# MCH_FPGA_Banks_224_225_226_227_228.net
KiCad netlist of a schematic drawn in Altium Designer
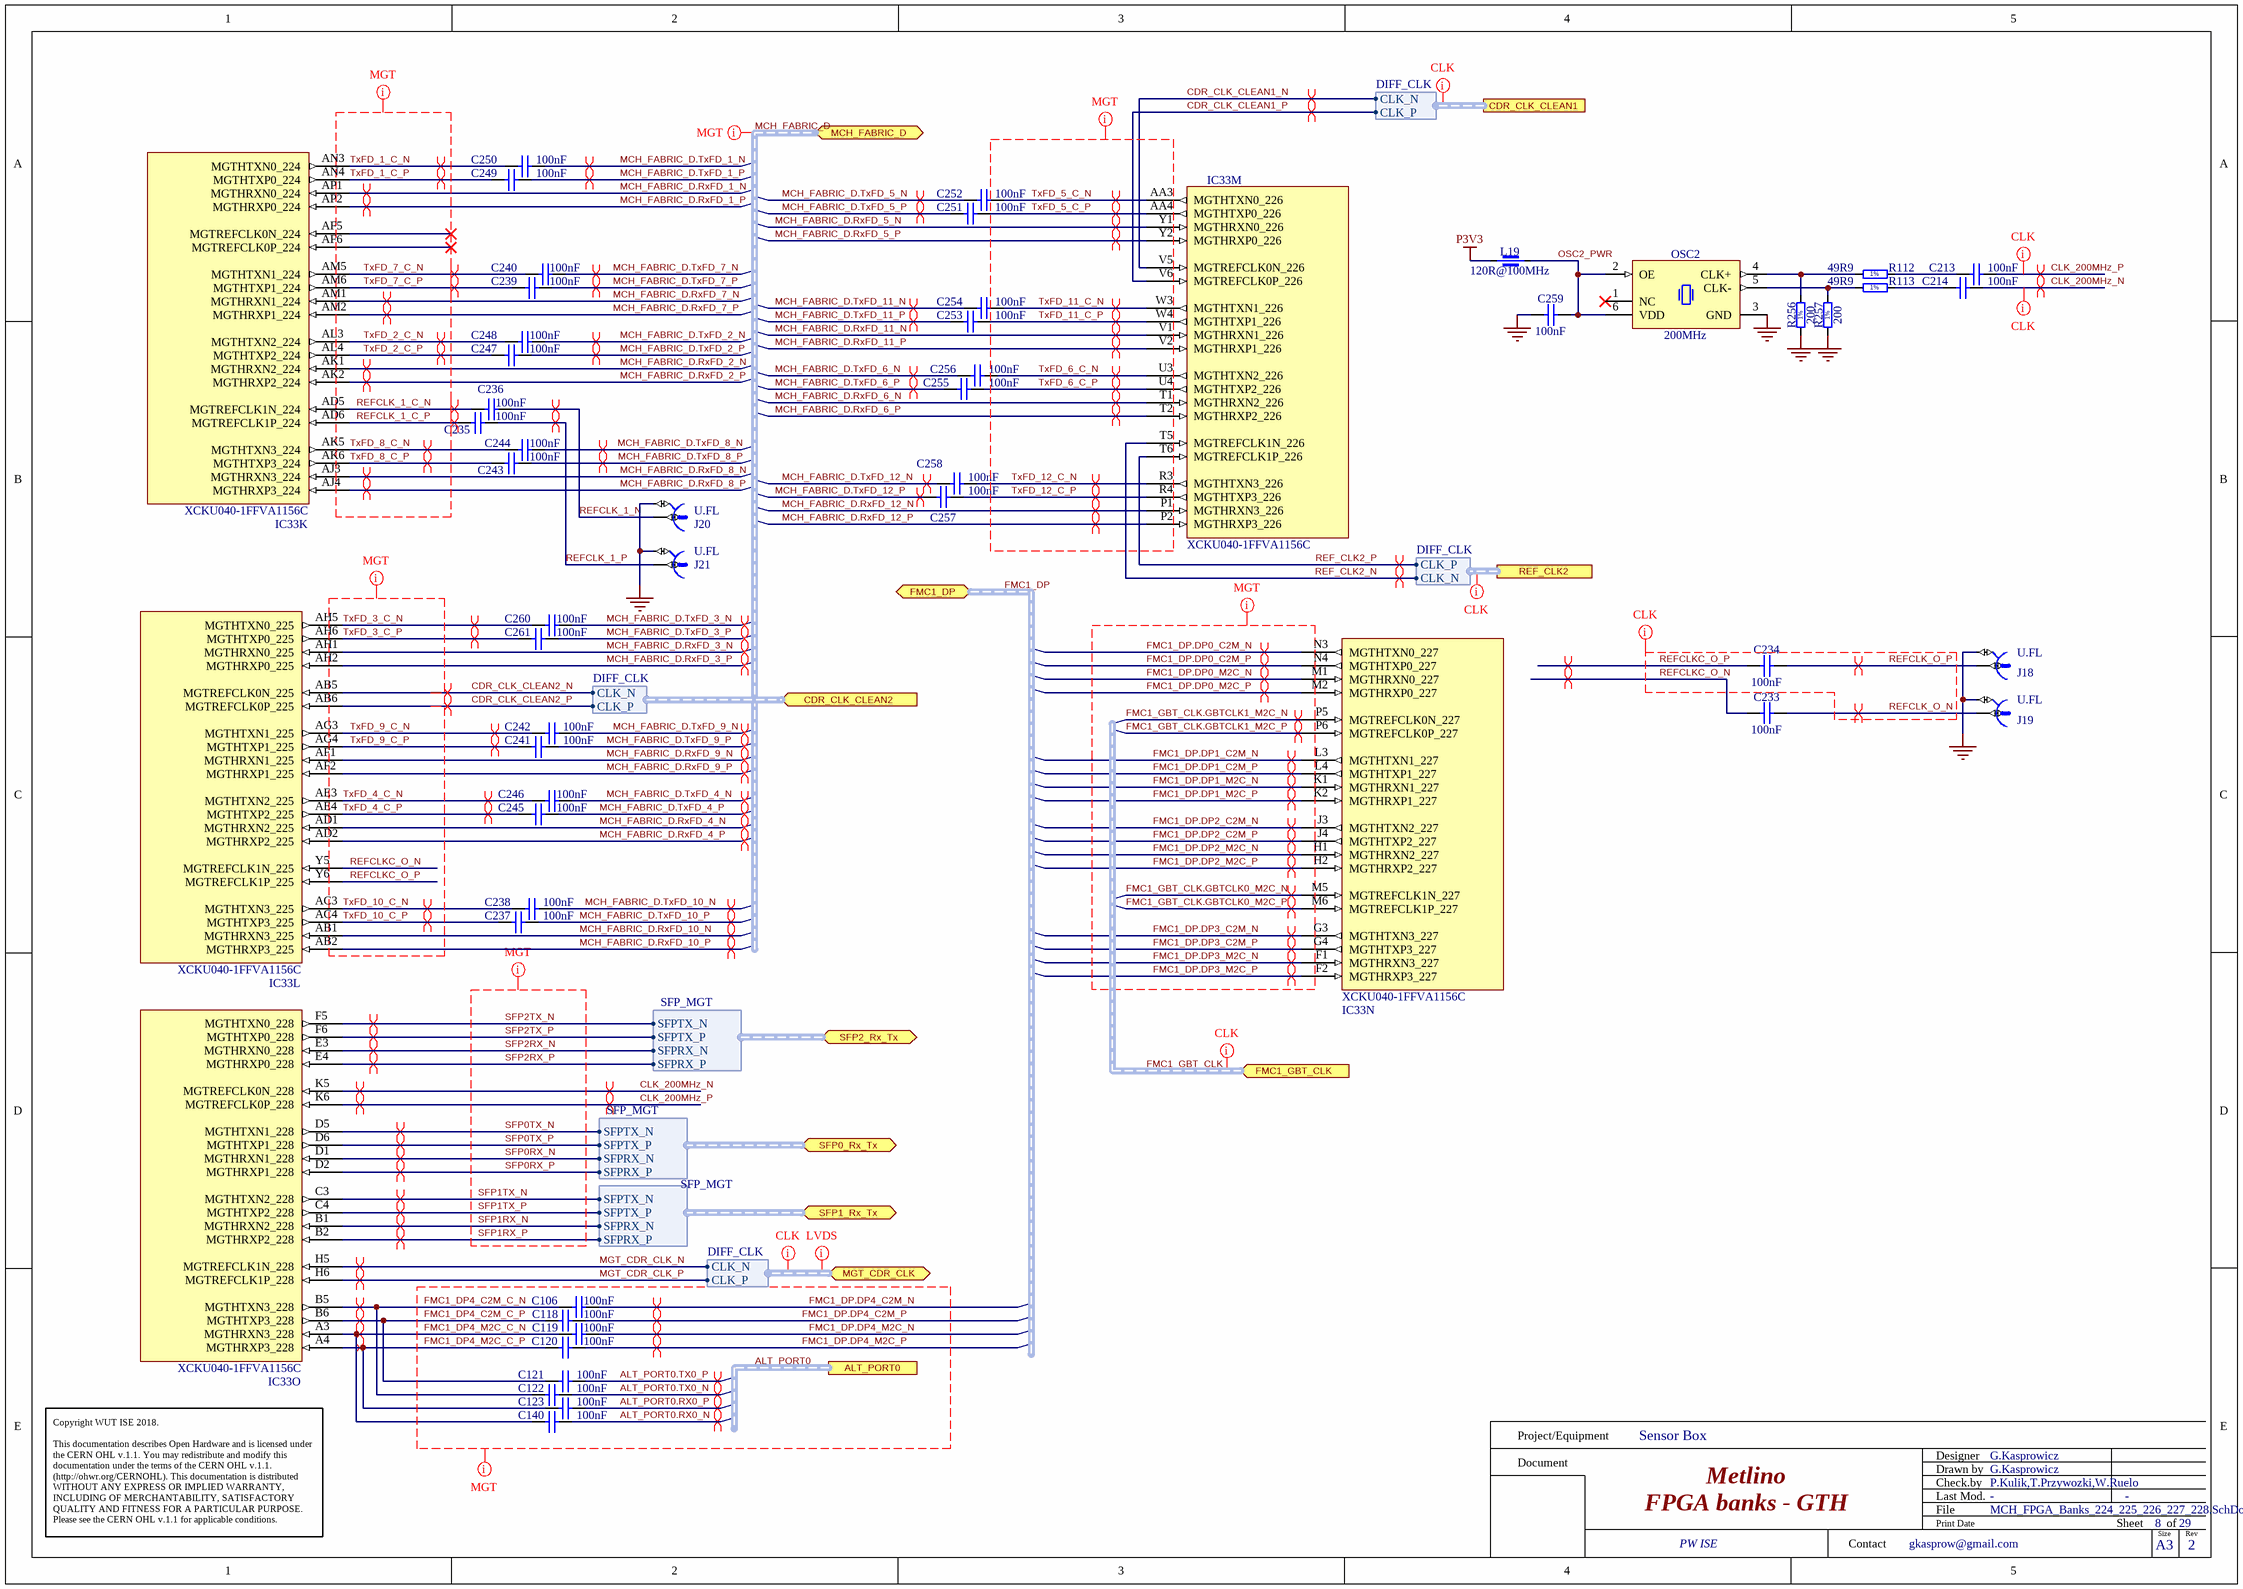
[diagram p0: MCH_FPGA_Banks_224_225_226_227_228.SchDoc]

(export (version "E")
  (design (tool "Eeschema 10.0.6"))
  (components
    (comp (ref "C106")
      (value "100nF")
      (footprint "CAPC0603X33N")
      (description "Non-polarised capacitor")
      (fields
        (field (name "MANUFACTURER PART NUMBER") "CC0201_100NF_6.3V_10%_X5R")
        (field (name "MANUFACTURER") "GENERIC")
        (field (name "AUTHOR") "CERN DEM JLC")
      )
      (libsource (lib "Capacitors") (part "Capacitor - non polarized"))
    )
    (comp (ref "C118")
      (value "100nF")
      (footprint "CAPC0603X33N")
      (description "Non-polarised capacitor")
      (fields
        (field (name "MANUFACTURER PART NUMBER") "CC0201_100NF_6.3V_10%_X5R")
        (field (name "MANUFACTURER") "GENERIC")
        (field (name "AUTHOR") "CERN DEM JLC")
      )
      (libsource (lib "Capacitors") (part "Capacitor - non polarized"))
    )
    (comp (ref "C119")
      (value "100nF")
      (footprint "CAPC0603X33N")
      (description "Non-polarised capacitor")
      (fields
        (field (name "MANUFACTURER PART NUMBER") "CC0201_100NF_6.3V_10%_X5R")
        (field (name "MANUFACTURER") "GENERIC")
        (field (name "AUTHOR") "CERN DEM JLC")
      )
      (libsource (lib "Capacitors") (part "Capacitor - non polarized"))
    )
    (comp (ref "C120")
      (value "100nF")
      (footprint "CAPC0603X33N")
      (description "Non-polarised capacitor")
      (fields
        (field (name "MANUFACTURER PART NUMBER") "CC0201_100NF_6.3V_10%_X5R")
        (field (name "MANUFACTURER") "GENERIC")
        (field (name "AUTHOR") "CERN DEM JLC")
      )
      (libsource (lib "Capacitors") (part "Capacitor - non polarized"))
    )
    (comp (ref "C121")
      (value "100nF")
      (footprint "CAPC0603X33N")
      (description "Non-polarised capacitor")
      (fields
        (field (name "MANUFACTURER PART NUMBER") "CC0201_100NF_6.3V_10%_X5R")
        (field (name "MANUFACTURER") "GENERIC")
        (field (name "AUTHOR") "CERN DEM JLC")
      )
      (libsource (lib "Capacitors") (part "Capacitor - non polarized"))
    )
    (comp (ref "C122")
      (value "100nF")
      (footprint "CAPC0603X33N")
      (description "Non-polarised capacitor")
      (fields
        (field (name "MANUFACTURER PART NUMBER") "CC0201_100NF_6.3V_10%_X5R")
        (field (name "MANUFACTURER") "GENERIC")
        (field (name "AUTHOR") "CERN DEM JLC")
      )
      (libsource (lib "Capacitors") (part "Capacitor - non polarized"))
    )
    (comp (ref "C123")
      (value "100nF")
      (footprint "CAPC0603X33N")
      (description "Non-polarised capacitor")
      (fields
        (field (name "MANUFACTURER PART NUMBER") "CC0201_100NF_6.3V_10%_X5R")
        (field (name "MANUFACTURER") "GENERIC")
        (field (name "AUTHOR") "CERN DEM JLC")
      )
      (libsource (lib "Capacitors") (part "Capacitor - non polarized"))
    )
    (comp (ref "C140")
      (value "100nF")
      (footprint "CAPC0603X33N")
      (description "Non-polarised capacitor")
      (fields
        (field (name "MANUFACTURER PART NUMBER") "CC0201_100NF_6.3V_10%_X5R")
        (field (name "MANUFACTURER") "GENERIC")
        (field (name "AUTHOR") "CERN DEM JLC")
      )
      (libsource (lib "Capacitors") (part "Capacitor - non polarized"))
    )
    (comp (ref "C213")
      (value "100nF")
      (footprint "CAPC0603X33N")
      (description "Non-polarised capacitor")
      (fields
        (field (name "MANUFACTURER PART NUMBER") "CC0201_100NF_6.3V_10%_X5R")
        (field (name "MANUFACTURER") "GENERIC")
        (field (name "AUTHOR") "CERN DEM JLC")
      )
      (libsource (lib "Capacitors") (part "Capacitor - non polarized"))
    )
    (comp (ref "C214")
      (value "100nF")
      (footprint "CAPC0603X33N")
      (description "Non-polarised capacitor")
      (fields
        (field (name "MANUFACTURER PART NUMBER") "CC0201_100NF_6.3V_10%_X5R")
        (field (name "MANUFACTURER") "GENERIC")
        (field (name "AUTHOR") "CERN DEM JLC")
      )
      (libsource (lib "Capacitors") (part "Capacitor - non polarized"))
    )
    (comp (ref "C233")
      (value "100nF")
      (footprint "CAPC0603X33N")
      (description "Non-polarised capacitor")
      (fields
        (field (name "MANUFACTURER PART NUMBER") "CC0201_100NF_6.3V_10%_X5R")
        (field (name "MANUFACTURER") "GENERIC")
        (field (name "AUTHOR") "CERN DEM JLC")
      )
      (libsource (lib "Capacitors") (part "Capacitor - non polarized"))
    )
    (comp (ref "C234")
      (value "100nF")
      (footprint "CAPC0603X33N")
      (description "Non-polarised capacitor")
      (fields
        (field (name "MANUFACTURER PART NUMBER") "CC0201_100NF_6.3V_10%_X5R")
        (field (name "MANUFACTURER") "GENERIC")
        (field (name "AUTHOR") "CERN DEM JLC")
      )
      (libsource (lib "Capacitors") (part "Capacitor - non polarized"))
    )
    (comp (ref "C235")
      (value "100nF")
      (footprint "CAPC0603X33N")
      (description "Non-polarised capacitor")
      (fields
        (field (name "MANUFACTURER PART NUMBER") "CC0201_100NF_6.3V_10%_X5R")
        (field (name "MANUFACTURER") "GENERIC")
        (field (name "AUTHOR") "CERN DEM JLC")
      )
      (libsource (lib "Capacitors") (part "Capacitor - non polarized"))
    )
    (comp (ref "C236")
      (value "100nF")
      (footprint "CAPC0603X33N")
      (description "Non-polarised capacitor")
      (fields
        (field (name "MANUFACTURER PART NUMBER") "CC0201_100NF_6.3V_10%_X5R")
        (field (name "MANUFACTURER") "GENERIC")
        (field (name "AUTHOR") "CERN DEM JLC")
      )
      (libsource (lib "Capacitors") (part "Capacitor - non polarized"))
    )
    (comp (ref "C237")
      (value "100nF")
      (footprint "CAPC0603X33N")
      (description "Non-polarised capacitor")
      (fields
        (field (name "MANUFACTURER PART NUMBER") "CC0201_100NF_6.3V_10%_X5R")
        (field (name "MANUFACTURER") "GENERIC")
        (field (name "AUTHOR") "CERN DEM JLC")
      )
      (libsource (lib "Capacitors") (part "Capacitor - non polarized"))
    )
    (comp (ref "C238")
      (value "100nF")
      (footprint "CAPC0603X33N")
      (description "Non-polarised capacitor")
      (fields
        (field (name "MANUFACTURER PART NUMBER") "CC0201_100NF_6.3V_10%_X5R")
        (field (name "MANUFACTURER") "GENERIC")
        (field (name "AUTHOR") "CERN DEM JLC")
      )
      (libsource (lib "Capacitors") (part "Capacitor - non polarized"))
    )
    (comp (ref "C239")
      (value "100nF")
      (footprint "CAPC0603X33N")
      (description "Non-polarised capacitor")
      (fields
        (field (name "MANUFACTURER PART NUMBER") "CC0201_100NF_6.3V_10%_X5R")
        (field (name "MANUFACTURER") "GENERIC")
        (field (name "AUTHOR") "CERN DEM JLC")
      )
      (libsource (lib "Capacitors") (part "Capacitor - non polarized"))
    )
    (comp (ref "C240")
      (value "100nF")
      (footprint "CAPC0603X33N")
      (description "Non-polarised capacitor")
      (fields
        (field (name "MANUFACTURER PART NUMBER") "CC0201_100NF_6.3V_10%_X5R")
        (field (name "MANUFACTURER") "GENERIC")
        (field (name "AUTHOR") "CERN DEM JLC")
      )
      (libsource (lib "Capacitors") (part "Capacitor - non polarized"))
    )
    (comp (ref "C241")
      (value "100nF")
      (footprint "CAPC0603X33N")
      (description "Non-polarised capacitor")
      (fields
        (field (name "MANUFACTURER PART NUMBER") "CC0201_100NF_6.3V_10%_X5R")
        (field (name "MANUFACTURER") "GENERIC")
        (field (name "AUTHOR") "CERN DEM JLC")
      )
      (libsource (lib "Capacitors") (part "Capacitor - non polarized"))
    )
    (comp (ref "C242")
      (value "100nF")
      (footprint "CAPC0603X33N")
      (description "Non-polarised capacitor")
      (fields
        (field (name "MANUFACTURER PART NUMBER") "CC0201_100NF_6.3V_10%_X5R")
        (field (name "MANUFACTURER") "GENERIC")
        (field (name "AUTHOR") "CERN DEM JLC")
      )
      (libsource (lib "Capacitors") (part "Capacitor - non polarized"))
    )
    (comp (ref "C243")
      (value "100nF")
      (footprint "CAPC0603X33N")
      (description "Non-polarised capacitor")
      (fields
        (field (name "MANUFACTURER PART NUMBER") "CC0201_100NF_6.3V_10%_X5R")
        (field (name "MANUFACTURER") "GENERIC")
        (field (name "AUTHOR") "CERN DEM JLC")
      )
      (libsource (lib "Capacitors") (part "Capacitor - non polarized"))
    )
    (comp (ref "C244")
      (value "100nF")
      (footprint "CAPC0603X33N")
      (description "Non-polarised capacitor")
      (fields
        (field (name "MANUFACTURER PART NUMBER") "CC0201_100NF_6.3V_10%_X5R")
        (field (name "MANUFACTURER") "GENERIC")
        (field (name "AUTHOR") "CERN DEM JLC")
      )
      (libsource (lib "Capacitors") (part "Capacitor - non polarized"))
    )
    (comp (ref "C245")
      (value "100nF")
      (footprint "CAPC0603X33N")
      (description "Non-polarised capacitor")
      (fields
        (field (name "MANUFACTURER PART NUMBER") "CC0201_100NF_6.3V_10%_X5R")
        (field (name "MANUFACTURER") "GENERIC")
        (field (name "AUTHOR") "CERN DEM JLC")
      )
      (libsource (lib "Capacitors") (part "Capacitor - non polarized"))
    )
    (comp (ref "C246")
      (value "100nF")
      (footprint "CAPC0603X33N")
      (description "Non-polarised capacitor")
      (fields
        (field (name "MANUFACTURER PART NUMBER") "CC0201_100NF_6.3V_10%_X5R")
        (field (name "MANUFACTURER") "GENERIC")
        (field (name "AUTHOR") "CERN DEM JLC")
      )
      (libsource (lib "Capacitors") (part "Capacitor - non polarized"))
    )
    (comp (ref "C247")
      (value "100nF")
      (footprint "CAPC0603X33N")
      (description "Non-polarised capacitor")
      (fields
        (field (name "MANUFACTURER PART NUMBER") "CC0201_100NF_6.3V_10%_X5R")
        (field (name "MANUFACTURER") "GENERIC")
        (field (name "AUTHOR") "CERN DEM JLC")
      )
      (libsource (lib "Capacitors") (part "Capacitor - non polarized"))
    )
    (comp (ref "C248")
      (value "100nF")
      (footprint "CAPC0603X33N")
      (description "Non-polarised capacitor")
      (fields
        (field (name "MANUFACTURER PART NUMBER") "CC0201_100NF_6.3V_10%_X5R")
        (field (name "MANUFACTURER") "GENERIC")
        (field (name "AUTHOR") "CERN DEM JLC")
      )
      (libsource (lib "Capacitors") (part "Capacitor - non polarized"))
    )
    (comp (ref "C249")
      (value "100nF")
      (footprint "CAPC0603X33N")
      (description "Non-polarised capacitor")
      (fields
        (field (name "MANUFACTURER PART NUMBER") "CC0201_100NF_6.3V_10%_X5R")
        (field (name "MANUFACTURER") "GENERIC")
        (field (name "AUTHOR") "CERN DEM JLC")
      )
      (libsource (lib "Capacitors") (part "Capacitor - non polarized"))
    )
    (comp (ref "C250")
      (value "100nF")
      (footprint "CAPC0603X33N")
      (description "Non-polarised capacitor")
      (fields
        (field (name "MANUFACTURER PART NUMBER") "CC0201_100NF_6.3V_10%_X5R")
        (field (name "MANUFACTURER") "GENERIC")
        (field (name "AUTHOR") "CERN DEM JLC")
      )
      (libsource (lib "Capacitors") (part "Capacitor - non polarized"))
    )
    (comp (ref "C251")
      (value "100nF")
      (footprint "CAPC0603X33N")
      (description "Non-polarised capacitor")
      (fields
        (field (name "MANUFACTURER PART NUMBER") "CC0201_100NF_6.3V_10%_X5R")
        (field (name "MANUFACTURER") "GENERIC")
        (field (name "AUTHOR") "CERN DEM JLC")
      )
      (libsource (lib "Capacitors") (part "Capacitor - non polarized"))
    )
    (comp (ref "C252")
      (value "100nF")
      (footprint "CAPC0603X33N")
      (description "Non-polarised capacitor")
      (fields
        (field (name "MANUFACTURER PART NUMBER") "CC0201_100NF_6.3V_10%_X5R")
        (field (name "MANUFACTURER") "GENERIC")
        (field (name "AUTHOR") "CERN DEM JLC")
      )
      (libsource (lib "Capacitors") (part "Capacitor - non polarized"))
    )
    (comp (ref "C253")
      (value "100nF")
      (footprint "CAPC0603X33N")
      (description "Non-polarised capacitor")
      (fields
        (field (name "MANUFACTURER PART NUMBER") "CC0201_100NF_6.3V_10%_X5R")
        (field (name "MANUFACTURER") "GENERIC")
        (field (name "AUTHOR") "CERN DEM JLC")
      )
      (libsource (lib "Capacitors") (part "Capacitor - non polarized"))
    )
    (comp (ref "C254")
      (value "100nF")
      (footprint "CAPC0603X33N")
      (description "Non-polarised capacitor")
      (fields
        (field (name "MANUFACTURER PART NUMBER") "CC0201_100NF_6.3V_10%_X5R")
        (field (name "MANUFACTURER") "GENERIC")
        (field (name "AUTHOR") "CERN DEM JLC")
      )
      (libsource (lib "Capacitors") (part "Capacitor - non polarized"))
    )
    (comp (ref "C255")
      (value "100nF")
      (footprint "CAPC0603X33N")
      (description "Non-polarised capacitor")
      (fields
        (field (name "MANUFACTURER PART NUMBER") "CC0201_100NF_6.3V_10%_X5R")
        (field (name "MANUFACTURER") "GENERIC")
        (field (name "AUTHOR") "CERN DEM JLC")
      )
      (libsource (lib "Capacitors") (part "Capacitor - non polarized"))
    )
    (comp (ref "C256")
      (value "100nF")
      (footprint "CAPC0603X33N")
      (description "Non-polarised capacitor")
      (fields
        (field (name "MANUFACTURER PART NUMBER") "CC0201_100NF_6.3V_10%_X5R")
        (field (name "MANUFACTURER") "GENERIC")
        (field (name "AUTHOR") "CERN DEM JLC")
      )
      (libsource (lib "Capacitors") (part "Capacitor - non polarized"))
    )
    (comp (ref "C257")
      (value "100nF")
      (footprint "CAPC0603X33N")
      (description "Non-polarised capacitor")
      (fields
        (field (name "MANUFACTURER PART NUMBER") "CC0201_100NF_6.3V_10%_X5R")
        (field (name "MANUFACTURER") "GENERIC")
        (field (name "AUTHOR") "CERN DEM JLC")
      )
      (libsource (lib "Capacitors") (part "Capacitor - non polarized"))
    )
    (comp (ref "C258")
      (value "100nF")
      (footprint "CAPC0603X33N")
      (description "Non-polarised capacitor")
      (fields
        (field (name "MANUFACTURER PART NUMBER") "CC0201_100NF_6.3V_10%_X5R")
        (field (name "MANUFACTURER") "GENERIC")
        (field (name "AUTHOR") "CERN DEM JLC")
      )
      (libsource (lib "Capacitors") (part "Capacitor - non polarized"))
    )
    (comp (ref "C259")
      (value "100nF")
      (footprint "CAPC0603X33N")
      (description "Non-polarised capacitor")
      (fields
        (field (name "MANUFACTURER PART NUMBER") "CC0201_100NF_6.3V_10%_X5R")
        (field (name "MANUFACTURER") "GENERIC")
        (field (name "AUTHOR") "CERN DEM JLC")
      )
      (libsource (lib "Capacitors") (part "Capacitor - non polarized"))
    )
    (comp (ref "C260")
      (value "100nF")
      (footprint "CAPC0603X33N")
      (description "Non-polarised capacitor")
      (fields
        (field (name "MANUFACTURER PART NUMBER") "CC0201_100NF_6.3V_10%_X5R")
        (field (name "MANUFACTURER") "GENERIC")
        (field (name "AUTHOR") "CERN DEM JLC")
      )
      (libsource (lib "Capacitors") (part "Capacitor - non polarized"))
    )
    (comp (ref "C261")
      (value "100nF")
      (footprint "CAPC0603X33N")
      (description "Non-polarised capacitor")
      (fields
        (field (name "MANUFACTURER PART NUMBER") "CC0201_100NF_6.3V_10%_X5R")
        (field (name "MANUFACTURER") "GENERIC")
        (field (name "AUTHOR") "CERN DEM JLC")
      )
      (libsource (lib "Capacitors") (part "Capacitor - non polarized"))
    )
    (comp (ref "IC33")
      (value "XCKU040-1FFVA1156C")
      (footprint "BGA1156C100P34X34_3500X3500X350")
      (description "Kintex UltraScale FPGA, 520 I/O, 530K Cells, 1156-Ball BGA, Speed Grade 1, Commercial Grade")
      (fields (field (name "MANUFACTURER") "XILINX") (field (name "AUTHOR") "CERN DEM CA"))
      (libsource (lib "ICs And Semiconductors") (part "XCKU040-1FFVA1156C"))
    )
    (comp (ref "J18")
      (value "U.FL")
      (footprint "HIROSE_U.FL-R-SMT-1(10)")
      (fields
        (field (name "MANUFACTURER PART NUMBER") "U.FL-R-SMT-1(10)")
        (field (name "MANUFACTURER") "HIROSE (HRS)")
        (field (name "PART NUMBER") "HIROSE_U.FL-R-SMT-1(10)")
        (field (name "AUTHOR") "CERN DEM JLC")
      )
      (libsource (lib "Connectors") (part "Coax_1Male_1Shield"))
    )
    (comp (ref "J19")
      (value "U.FL")
      (footprint "HIROSE_U.FL-R-SMT-1(10)")
      (fields
        (field (name "MANUFACTURER PART NUMBER") "U.FL-R-SMT-1(10)")
        (field (name "MANUFACTURER") "HIROSE (HRS)")
        (field (name "PART NUMBER") "HIROSE_U.FL-R-SMT-1(10)")
        (field (name "AUTHOR") "CERN DEM JLC")
      )
      (libsource (lib "Connectors") (part "Coax_1Male_1Shield"))
    )
    (comp (ref "J20")
      (value "U.FL")
      (footprint "HIROSE_U.FL-R-SMT-1(10)")
      (fields
        (field (name "MANUFACTURER PART NUMBER") "U.FL-R-SMT-1(10)")
        (field (name "MANUFACTURER") "HIROSE (HRS)")
        (field (name "PART NUMBER") "HIROSE_U.FL-R-SMT-1(10)")
        (field (name "AUTHOR") "CERN DEM JLC")
      )
      (libsource (lib "Connectors") (part "Coax_1Male_1Shield"))
    )
    (comp (ref "J21")
      (value "U.FL")
      (footprint "HIROSE_U.FL-R-SMT-1(10)")
      (fields
        (field (name "MANUFACTURER PART NUMBER") "U.FL-R-SMT-1(10)")
        (field (name "MANUFACTURER") "HIROSE (HRS)")
        (field (name "PART NUMBER") "HIROSE_U.FL-R-SMT-1(10)")
        (field (name "AUTHOR") "CERN DEM JLC")
      )
      (libsource (lib "Connectors") (part "Coax_1Male_1Shield"))
    )
    (comp (ref "L19")
      (value "120R@100MHz")
      (footprint "INDC1005X55N")
      (fields
        (field (name "MANUFACTURER PART NUMBER") "BLM15PX121SN1D")
        (field (name "MANUFACTURER") "MURATA")
        (field (name "PART NUMBER") "IND0402_MURATA_BLM15PX121SN1D")
        (field (name "AUTHOR") "CERN DEM JMW")
      )
      (libsource (lib "Inductors & Transformers") (part "Ferrite Bead"))
    )
    (comp (ref "OSC2")
      (value "200MHz")
      (footprint "OSC_SILICON-LAB_SI510-6N(5X7)")
      (description "Crystal Oscillator 6 pins, Si510 (LVDS/LVPECL/HCSL/Dual CMOS)")
      (fields
        (field (name "MANUFACTURER PART NUMBER") "510ABA200M000AAG")
        (field (name "MANUFACTURER") "SILICON LABS")
        (field (name "AUTHOR") "GK")
      )
      (libsource (lib "LIBRARY_SCH") (part "OSC_200MHZ_SILICON-LAB_510ABA200M000AAG"))
    )
    (comp (ref "R112")
      (value "49R9")
      (footprint "RESC1005X40N")
      (description "Resistor - 1%")
      (fields
        (field (name "PART NUMBER") "R0402_49R9_1%_0.0625W_100PPM")
        (field (name "POWER") "0.0625W")
        (field (name "AUTHOR") "CERN DEM JLC")
      )
      (libsource (lib "Resistors") (part "Resistor - 1%"))
    )
    (comp (ref "R113")
      (value "49R9")
      (footprint "RESC1005X40N")
      (description "Resistor - 1%")
      (fields
        (field (name "PART NUMBER") "R0402_49R9_1%_0.0625W_100PPM")
        (field (name "POWER") "0.0625W")
        (field (name "AUTHOR") "CERN DEM JLC")
      )
      (libsource (lib "Resistors") (part "Resistor - 1%"))
    )
    (comp (ref "R256")
      (value "200")
      (footprint "RESC1005X40N")
      (description "Resistor - 1%")
      (fields
        (field (name "MANUFACTURER PART NUMBER") "R0402_200R_1%_0.0625W_100PPM")
        (field (name "MANUFACTURER") "GENERIC")
        (field (name "AUTHOR") "CERN DEM JLC")
      )
      (libsource (lib "Resistors") (part "Resistor - 1%"))
    )
    (comp (ref "R257")
      (value "200")
      (footprint "RESC1005X40N")
      (description "Resistor - 1%")
      (fields
        (field (name "MANUFACTURER PART NUMBER") "R0402_200R_1%_0.0625W_100PPM")
        (field (name "MANUFACTURER") "GENERIC")
        (field (name "AUTHOR") "CERN DEM JLC")
      )
      (libsource (lib "Resistors") (part "Resistor - 1%"))
    )
  )
  (nets
    (net (code "7") (name "/ALT_PORT0.RX0_N") (class "Default")
      (node (ref "C140") (pin "2") (pinfunction "2_2") (pintype "passive"))
    )
    (net (code "8") (name "/ALT_PORT0.RX0_P") (class "Default")
      (node (ref "C123") (pin "2") (pinfunction "2_2") (pintype "passive"))
    )
    (net (code "9") (name "/ALT_PORT0.TX0_N") (class "Default")
      (node (ref "C122") (pin "2") (pinfunction "2_2") (pintype "passive"))
    )
    (net (code "10") (name "/ALT_PORT0.TX0_P") (class "Default")
      (node (ref "C121") (pin "2") (pinfunction "2_2") (pintype "passive"))
    )
    (net (code "11") (name "/CDR_CLK_CLEAN1_N") (class "Default")
      (node (ref "IC33") (pin "V5") (pinfunction "MGTREFCLK0N_226_V5") (pintype "input"))
    )
    (net (code "12") (name "/CDR_CLK_CLEAN1_P") (class "Default")
      (node (ref "IC33") (pin "V6") (pinfunction "MGTREFCLK0P_226_V6") (pintype "input"))
    )
    (net (code "13") (name "/CDR_CLK_CLEAN2_N") (class "Default")
      (node (ref "IC33") (pin "AB5") (pinfunction "MGTREFCLK0N_225_AB5") (pintype "input"))
    )
    (net (code "14") (name "/CDR_CLK_CLEAN2_P") (class "Default")
      (node (ref "IC33") (pin "AB6") (pinfunction "MGTREFCLK0P_225_AB6") (pintype "input"))
    )
    (net (code "15") (name "/CLK_200MHz_N") (class "Default")
      (node (ref "C214") (pin "2") (pinfunction "2_2") (pintype "passive"))
      (node (ref "IC33") (pin "K5") (pinfunction "MGTREFCLK0N_228_K5") (pintype "input"))
    )
    (net (code "16") (name "/CLK_200MHz_P") (class "Default")
      (node (ref "C213") (pin "2") (pinfunction "2_2") (pintype "passive"))
      (node (ref "IC33") (pin "K6") (pinfunction "MGTREFCLK0P_228_K6") (pintype "input"))
    )
    (net (code "17") (name "/FMC1_DP.DP0_C2M_N") (class "Default")
      (node (ref "IC33") (pin "N3") (pinfunction "MGTHTXN0_227_N3") (pintype "output"))
    )
    (net (code "18") (name "/FMC1_DP.DP0_C2M_P") (class "Default")
      (node (ref "IC33") (pin "N4") (pinfunction "MGTHTXP0_227_N4") (pintype "output"))
    )
    (net (code "19") (name "/FMC1_DP.DP0_M2C_N") (class "Default")
      (node (ref "IC33") (pin "M1") (pinfunction "MGTHRXN0_227_M1") (pintype "input"))
    )
    (net (code "20") (name "/FMC1_DP.DP0_M2C_P") (class "Default")
      (node (ref "IC33") (pin "M2") (pinfunction "MGTHRXP0_227_M2") (pintype "input"))
    )
    (net (code "21") (name "/FMC1_DP.DP1_C2M_N") (class "Default")
      (node (ref "IC33") (pin "L3") (pinfunction "MGTHTXN1_227_L3") (pintype "output"))
    )
    (net (code "22") (name "/FMC1_DP.DP1_C2M_P") (class "Default")
      (node (ref "IC33") (pin "L4") (pinfunction "MGTHTXP1_227_L4") (pintype "output"))
    )
    (net (code "23") (name "/FMC1_DP.DP1_M2C_N") (class "Default")
      (node (ref "IC33") (pin "K1") (pinfunction "MGTHRXN1_227_K1") (pintype "input"))
    )
    (net (code "24") (name "/FMC1_DP.DP1_M2C_P") (class "Default")
      (node (ref "IC33") (pin "K2") (pinfunction "MGTHRXP1_227_K2") (pintype "input"))
    )
    (net (code "25") (name "/FMC1_DP.DP2_C2M_N") (class "Default")
      (node (ref "IC33") (pin "J3") (pinfunction "MGTHTXN2_227_J3") (pintype "output"))
    )
    (net (code "26") (name "/FMC1_DP.DP2_C2M_P") (class "Default")
      (node (ref "IC33") (pin "J4") (pinfunction "MGTHTXP2_227_J4") (pintype "output"))
    )
    (net (code "27") (name "/FMC1_DP.DP2_M2C_N") (class "Default")
      (node (ref "IC33") (pin "H1") (pinfunction "MGTHRXN2_227_H1") (pintype "input"))
    )
    (net (code "28") (name "/FMC1_DP.DP2_M2C_P") (class "Default")
      (node (ref "IC33") (pin "H2") (pinfunction "MGTHRXP2_227_H2") (pintype "input"))
    )
    (net (code "29") (name "/FMC1_DP.DP3_C2M_N") (class "Default")
      (node (ref "IC33") (pin "G3") (pinfunction "MGTHTXN3_227_G3") (pintype "output"))
    )
    (net (code "30") (name "/FMC1_DP.DP3_C2M_P") (class "Default")
      (node (ref "IC33") (pin "G4") (pinfunction "MGTHTXP3_227_G4") (pintype "output"))
    )
    (net (code "31") (name "/FMC1_DP.DP3_M2C_N") (class "Default")
      (node (ref "IC33") (pin "F1") (pinfunction "MGTHRXN3_227_F1") (pintype "input"))
    )
    (net (code "32") (name "/FMC1_DP.DP3_M2C_P") (class "Default")
      (node (ref "IC33") (pin "F2") (pinfunction "MGTHRXP3_227_F2") (pintype "input"))
    )
    (net (code "33") (name "/FMC1_DP.DP4_C2M_N") (class "Default")
      (node (ref "C106") (pin "2") (pinfunction "2_2") (pintype "passive"))
    )
    (net (code "34") (name "/FMC1_DP.DP4_C2M_P") (class "Default")
      (node (ref "C118") (pin "2") (pinfunction "2_2") (pintype "passive"))
    )
    (net (code "35") (name "/FMC1_DP.DP4_M2C_N") (class "Default")
      (node (ref "C119") (pin "2") (pinfunction "2_2") (pintype "passive"))
    )
    (net (code "36") (name "/FMC1_DP.DP4_M2C_P") (class "Default")
      (node (ref "C120") (pin "2") (pinfunction "2_2") (pintype "passive"))
    )
    (net (code "37") (name "/FMC1_DP4_C2M_C_N") (class "Default")
      (node (ref "C106") (pin "1") (pinfunction "1_1") (pintype "passive"))
      (node (ref "C122") (pin "1") (pinfunction "1_1") (pintype "passive"))
      (node (ref "IC33") (pin "B5") (pinfunction "MGTHTXN3_228_B5") (pintype "output"))
    )
    (net (code "38") (name "/FMC1_DP4_C2M_C_P") (class "Default")
      (node (ref "C118") (pin "1") (pinfunction "1_1") (pintype "passive"))
      (node (ref "C121") (pin "1") (pinfunction "1_1") (pintype "passive"))
      (node (ref "IC33") (pin "B6") (pinfunction "MGTHTXP3_228_B6") (pintype "output"))
    )
    (net (code "39") (name "/FMC1_DP4_M2C_C_N") (class "Default")
      (node (ref "C119") (pin "1") (pinfunction "1_1") (pintype "passive"))
      (node (ref "C140") (pin "1") (pinfunction "1_1") (pintype "passive"))
      (node (ref "IC33") (pin "A3") (pinfunction "MGTHRXN3_228_A3") (pintype "input"))
    )
    (net (code "40") (name "/FMC1_DP4_M2C_C_P") (class "Default")
      (node (ref "C120") (pin "1") (pinfunction "1_1") (pintype "passive"))
      (node (ref "C123") (pin "1") (pinfunction "1_1") (pintype "passive"))
      (node (ref "IC33") (pin "A4") (pinfunction "MGTHRXP3_228_A4") (pintype "input"))
    )
    (net (code "41") (name "/FMC1_GBT_CLK.GBTCLK0_M2C_N") (class "Default")
      (node (ref "IC33") (pin "M5") (pinfunction "MGTREFCLK1N_227_M5") (pintype "input"))
    )
    (net (code "42") (name "/FMC1_GBT_CLK.GBTCLK0_M2C_P") (class "Default")
      (node (ref "IC33") (pin "M6") (pinfunction "MGTREFCLK1P_227_M6") (pintype "input"))
    )
    (net (code "43") (name "/FMC1_GBT_CLK.GBTCLK1_M2C_N") (class "Default")
      (node (ref "IC33") (pin "P5") (pinfunction "MGTREFCLK0N_227_P5") (pintype "input"))
    )
    (net (code "44") (name "/FMC1_GBT_CLK.GBTCLK1_M2C_P") (class "Default")
      (node (ref "IC33") (pin "P6") (pinfunction "MGTREFCLK0P_227_P6") (pintype "input"))
    )
    (net (code "45") (name "/MCH_FABRIC_D.RxFD_1_N") (class "Default")
      (node (ref "IC33") (pin "AP1") (pinfunction "MGTHRXN0_224_AP1") (pintype "input"))
    )
    (net (code "46") (name "/MCH_FABRIC_D.RxFD_1_P") (class "Default")
      (node (ref "IC33") (pin "AP2") (pinfunction "MGTHRXP0_224_AP2") (pintype "input"))
    )
    (net (code "47") (name "/MCH_FABRIC_D.RxFD_2_N") (class "Default")
      (node (ref "IC33") (pin "AK1") (pinfunction "MGTHRXN2_224_AK1") (pintype "input"))
    )
    (net (code "48") (name "/MCH_FABRIC_D.RxFD_2_P") (class "Default")
      (node (ref "IC33") (pin "AK2") (pinfunction "MGTHRXP2_224_AK2") (pintype "input"))
    )
    (net (code "49") (name "/MCH_FABRIC_D.RxFD_3_N") (class "Default")
      (node (ref "IC33") (pin "AH1") (pinfunction "MGTHRXN0_225_AH1") (pintype "input"))
    )
    (net (code "50") (name "/MCH_FABRIC_D.RxFD_3_P") (class "Default")
      (node (ref "IC33") (pin "AH2") (pinfunction "MGTHRXP0_225_AH2") (pintype "input"))
    )
    (net (code "51") (name "/MCH_FABRIC_D.RxFD_4_N") (class "Default")
      (node (ref "IC33") (pin "AD1") (pinfunction "MGTHRXN2_225_AD1") (pintype "input"))
    )
    (net (code "52") (name "/MCH_FABRIC_D.RxFD_4_P") (class "Default")
      (node (ref "IC33") (pin "AD2") (pinfunction "MGTHRXP2_225_AD2") (pintype "input"))
    )
    (net (code "53") (name "/MCH_FABRIC_D.RxFD_5_N") (class "Default")
      (node (ref "IC33") (pin "Y1") (pinfunction "MGTHRXN0_226_Y1") (pintype "input"))
    )
    (net (code "54") (name "/MCH_FABRIC_D.RxFD_5_P") (class "Default")
      (node (ref "IC33") (pin "Y2") (pinfunction "MGTHRXP0_226_Y2") (pintype "input"))
    )
    (net (code "55") (name "/MCH_FABRIC_D.RxFD_6_N") (class "Default")
      (node (ref "IC33") (pin "T1") (pinfunction "MGTHRXN2_226_T1") (pintype "input"))
    )
    (net (code "56") (name "/MCH_FABRIC_D.RxFD_6_P") (class "Default")
      (node (ref "IC33") (pin "T2") (pinfunction "MGTHRXP2_226_T2") (pintype "input"))
    )
    (net (code "57") (name "/MCH_FABRIC_D.RxFD_7_N") (class "Default")
      (node (ref "IC33") (pin "AM1") (pinfunction "MGTHRXN1_224_AM1") (pintype "input"))
    )
    (net (code "58") (name "/MCH_FABRIC_D.RxFD_7_P") (class "Default")
      (node (ref "IC33") (pin "AM2") (pinfunction "MGTHRXP1_224_AM2") (pintype "input"))
    )
    (net (code "59") (name "/MCH_FABRIC_D.RxFD_8_N") (class "Default")
      (node (ref "IC33") (pin "AJ3") (pinfunction "MGTHRXN3_224_AJ3") (pintype "input"))
    )
    (net (code "60") (name "/MCH_FABRIC_D.RxFD_8_P") (class "Default")
      (node (ref "IC33") (pin "AJ4") (pinfunction "MGTHRXP3_224_AJ4") (pintype "input"))
    )
    (net (code "61") (name "/MCH_FABRIC_D.RxFD_9_N") (class "Default")
      (node (ref "IC33") (pin "AF1") (pinfunction "MGTHRXN1_225_AF1") (pintype "input"))
    )
    (net (code "62") (name "/MCH_FABRIC_D.RxFD_9_P") (class "Default")
      (node (ref "IC33") (pin "AF2") (pinfunction "MGTHRXP1_225_AF2") (pintype "input"))
    )
    (net (code "63") (name "/MCH_FABRIC_D.RxFD_10_N") (class "Default")
      (node (ref "IC33") (pin "AB1") (pinfunction "MGTHRXN3_225_AB1") (pintype "input"))
    )
    (net (code "64") (name "/MCH_FABRIC_D.RxFD_10_P") (class "Default")
      (node (ref "IC33") (pin "AB2") (pinfunction "MGTHRXP3_225_AB2") (pintype "input"))
    )
    (net (code "65") (name "/MCH_FABRIC_D.RxFD_11_N") (class "Default")
      (node (ref "IC33") (pin "V1") (pinfunction "MGTHRXN1_226_V1") (pintype "input"))
    )
    (net (code "66") (name "/MCH_FABRIC_D.RxFD_11_P") (class "Default")
      (node (ref "IC33") (pin "V2") (pinfunction "MGTHRXP1_226_V2") (pintype "input"))
    )
    (net (code "67") (name "/MCH_FABRIC_D.RxFD_12_N") (class "Default")
      (node (ref "IC33") (pin "P1") (pinfunction "MGTHRXN3_226_P1") (pintype "input"))
    )
    (net (code "68") (name "/MCH_FABRIC_D.RxFD_12_P") (class "Default")
      (node (ref "IC33") (pin "P2") (pinfunction "MGTHRXP3_226_P2") (pintype "input"))
    )
    (net (code "69") (name "/MCH_FABRIC_D.TxFD_1_N") (class "Default")
      (node (ref "C250") (pin "2") (pinfunction "2_2") (pintype "passive"))
    )
    (net (code "70") (name "/MCH_FABRIC_D.TxFD_1_P") (class "Default")
      (node (ref "C249") (pin "2") (pinfunction "2_2") (pintype "passive"))
    )
    (net (code "71") (name "/MCH_FABRIC_D.TxFD_2_N") (class "Default")
      (node (ref "C248") (pin "2") (pinfunction "2_2") (pintype "passive"))
    )
    (net (code "72") (name "/MCH_FABRIC_D.TxFD_2_P") (class "Default")
      (node (ref "C247") (pin "2") (pinfunction "2_2") (pintype "passive"))
    )
    (net (code "73") (name "/MCH_FABRIC_D.TxFD_3_N") (class "Default")
      (node (ref "C260") (pin "2") (pinfunction "2_2") (pintype "passive"))
    )
    (net (code "74") (name "/MCH_FABRIC_D.TxFD_3_P") (class "Default")
      (node (ref "C261") (pin "2") (pinfunction "2_2") (pintype "passive"))
    )
    (net (code "75") (name "/MCH_FABRIC_D.TxFD_4_N") (class "Default")
      (node (ref "C246") (pin "2") (pinfunction "2_2") (pintype "passive"))
    )
    (net (code "76") (name "/MCH_FABRIC_D.TxFD_4_P") (class "Default")
      (node (ref "C245") (pin "2") (pinfunction "2_2") (pintype "passive"))
    )
    (net (code "77") (name "/MCH_FABRIC_D.TxFD_5_N") (class "Default")
      (node (ref "C252") (pin "1") (pinfunction "1_1") (pintype "passive"))
    )
    (net (code "78") (name "/MCH_FABRIC_D.TxFD_5_P") (class "Default")
      (node (ref "C251") (pin "1") (pinfunction "1_1") (pintype "passive"))
    )
    (net (code "79") (name "/MCH_FABRIC_D.TxFD_6_N") (class "Default")
      (node (ref "C256") (pin "1") (pinfunction "1_1") (pintype "passive"))
    )
    (net (code "80") (name "/MCH_FABRIC_D.TxFD_6_P") (class "Default")
      (node (ref "C255") (pin "1") (pinfunction "1_1") (pintype "passive"))
    )
    (net (code "81") (name "/MCH_FABRIC_D.TxFD_7_N") (class "Default")
      (node (ref "C240") (pin "2") (pinfunction "2_2") (pintype "passive"))
    )
    (net (code "82") (name "/MCH_FABRIC_D.TxFD_7_P") (class "Default")
      (node (ref "C239") (pin "2") (pinfunction "2_2") (pintype "passive"))
    )
    (net (code "83") (name "/MCH_FABRIC_D.TxFD_8_N") (class "Default")
      (node (ref "C244") (pin "2") (pinfunction "2_2") (pintype "passive"))
    )
    (net (code "84") (name "/MCH_FABRIC_D.TxFD_8_P") (class "Default")
      (node (ref "C243") (pin "2") (pinfunction "2_2") (pintype "passive"))
    )
    (net (code "85") (name "/MCH_FABRIC_D.TxFD_9_N") (class "Default")
      (node (ref "C242") (pin "2") (pinfunction "2_2") (pintype "passive"))
    )
    (net (code "86") (name "/MCH_FABRIC_D.TxFD_9_P") (class "Default")
      (node (ref "C241") (pin "2") (pinfunction "2_2") (pintype "passive"))
    )
    (net (code "87") (name "/MCH_FABRIC_D.TxFD_10_N") (class "Default")
      (node (ref "C238") (pin "2") (pinfunction "2_2") (pintype "passive"))
    )
    (net (code "88") (name "/MCH_FABRIC_D.TxFD_10_P") (class "Default")
      (node (ref "C237") (pin "2") (pinfunction "2_2") (pintype "passive"))
    )
    (net (code "89") (name "/MCH_FABRIC_D.TxFD_11_N") (class "Default")
      (node (ref "C254") (pin "1") (pinfunction "1_1") (pintype "passive"))
    )
    (net (code "90") (name "/MCH_FABRIC_D.TxFD_11_P") (class "Default")
      (node (ref "C253") (pin "1") (pinfunction "1_1") (pintype "passive"))
    )
    (net (code "91") (name "/MCH_FABRIC_D.TxFD_12_N") (class "Default")
      (node (ref "C258") (pin "1") (pinfunction "1_1") (pintype "passive"))
    )
    (net (code "92") (name "/MCH_FABRIC_D.TxFD_12_P") (class "Default")
      (node (ref "C257") (pin "1") (pinfunction "1_1") (pintype "passive"))
    )
    (net (code "93") (name "/MGT_CDR_CLK_N") (class "Default")
      (node (ref "IC33") (pin "H5") (pinfunction "MGTREFCLK1N_228_H5") (pintype "input"))
    )
    (net (code "94") (name "/MGT_CDR_CLK_P") (class "Default")
      (node (ref "IC33") (pin "H6") (pinfunction "MGTREFCLK1P_228_H6") (pintype "input"))
    )
    (net (code "95") (name "/OSC2_PWR") (class "Default")
      (node (ref "C259") (pin "2") (pinfunction "2_2") (pintype "passive"))
      (node (ref "L19") (pin "2") (pinfunction "2_2") (pintype "passive"))
      (node (ref "OSC2") (pin "2") (pinfunction "OE_2") (pintype "input"))
      (node (ref "OSC2") (pin "6") (pinfunction "VDD_6") (pintype "power_in"))
    )
    (net (code "96") (name "/REFCLKC_O_N") (class "Default")
      (node (ref "C233") (pin "1") (pinfunction "1_1") (pintype "passive"))
      (node (ref "IC33") (pin "Y5") (pinfunction "MGTREFCLK1N_225_Y5") (pintype "input"))
    )
    (net (code "97") (name "/REFCLKC_O_P") (class "Default")
      (node (ref "C234") (pin "1") (pinfunction "1_1") (pintype "passive"))
      (node (ref "IC33") (pin "Y6") (pinfunction "MGTREFCLK1P_225_Y6") (pintype "input"))
    )
    (net (code "98") (name "/REFCLK_1_C_N") (class "Default")
      (node (ref "C236") (pin "1") (pinfunction "1_1") (pintype "passive"))
      (node (ref "IC33") (pin "AD5") (pinfunction "MGTREFCLK1N_224_AD5") (pintype "input"))
    )
    (net (code "99") (name "/REFCLK_1_C_P") (class "Default")
      (node (ref "C235") (pin "1") (pinfunction "1_1") (pintype "passive"))
      (node (ref "IC33") (pin "AD6") (pinfunction "MGTREFCLK1P_224_AD6") (pintype "input"))
    )
    (net (code "100") (name "/REFCLK_1_N") (class "Default")
      (node (ref "C236") (pin "2") (pinfunction "2_2") (pintype "passive"))
      (node (ref "J20") (pin "1") (pinfunction "1_1") (pintype "bidirectional"))
    )
    (net (code "101") (name "/REFCLK_1_P") (class "Default")
      (node (ref "C235") (pin "2") (pinfunction "2_2") (pintype "passive"))
      (node (ref "J21") (pin "1") (pinfunction "1_1") (pintype "bidirectional"))
    )
    (net (code "102") (name "/REFCLK_O_N") (class "Default")
      (node (ref "C233") (pin "2") (pinfunction "2_2") (pintype "passive"))
      (node (ref "J19") (pin "1") (pinfunction "1_1") (pintype "bidirectional"))
    )
    (net (code "103") (name "/REFCLK_O_P") (class "Default")
      (node (ref "C234") (pin "2") (pinfunction "2_2") (pintype "passive"))
      (node (ref "J18") (pin "1") (pinfunction "1_1") (pintype "bidirectional"))
    )
    (net (code "104") (name "/REF_CLK2_N") (class "Default")
      (node (ref "IC33") (pin "T5") (pinfunction "MGTREFCLK1N_226_T5") (pintype "input"))
    )
    (net (code "105") (name "/REF_CLK2_P") (class "Default")
      (node (ref "IC33") (pin "T6") (pinfunction "MGTREFCLK1P_226_T6") (pintype "input"))
    )
    (net (code "106") (name "/SFP0RX_N") (class "Default")
      (node (ref "IC33") (pin "D1") (pinfunction "MGTHRXN1_228_D1") (pintype "input"))
    )
    (net (code "107") (name "/SFP0RX_P") (class "Default")
      (node (ref "IC33") (pin "D2") (pinfunction "MGTHRXP1_228_D2") (pintype "input"))
    )
    (net (code "108") (name "/SFP0TX_N") (class "Default")
      (node (ref "IC33") (pin "D5") (pinfunction "MGTHTXN1_228_D5") (pintype "output"))
    )
    (net (code "109") (name "/SFP0TX_P") (class "Default")
      (node (ref "IC33") (pin "D6") (pinfunction "MGTHTXP1_228_D6") (pintype "output"))
    )
    (net (code "110") (name "/SFP1RX_N") (class "Default")
      (node (ref "IC33") (pin "B1") (pinfunction "MGTHRXN2_228_B1") (pintype "input"))
    )
    (net (code "111") (name "/SFP1RX_P") (class "Default")
      (node (ref "IC33") (pin "B2") (pinfunction "MGTHRXP2_228_B2") (pintype "input"))
    )
    (net (code "112") (name "/SFP1TX_N") (class "Default")
      (node (ref "IC33") (pin "C3") (pinfunction "MGTHTXN2_228_C3") (pintype "output"))
    )
    (net (code "113") (name "/SFP1TX_P") (class "Default")
      (node (ref "IC33") (pin "C4") (pinfunction "MGTHTXP2_228_C4") (pintype "output"))
    )
    (net (code "114") (name "/SFP2RX_N") (class "Default")
      (node (ref "IC33") (pin "E3") (pinfunction "MGTHRXN0_228_E3") (pintype "input"))
    )
    (net (code "115") (name "/SFP2RX_P") (class "Default")
      (node (ref "IC33") (pin "E4") (pinfunction "MGTHRXP0_228_E4") (pintype "input"))
    )
    (net (code "116") (name "/SFP2TX_N") (class "Default")
      (node (ref "IC33") (pin "F5") (pinfunction "MGTHTXN0_228_F5") (pintype "output"))
    )
    (net (code "117") (name "/SFP2TX_P") (class "Default")
      (node (ref "IC33") (pin "F6") (pinfunction "MGTHTXP0_228_F6") (pintype "output"))
    )
    (net (code "118") (name "/TxFD_1_C_N") (class "Default")
      (node (ref "C250") (pin "1") (pinfunction "1_1") (pintype "passive"))
      (node (ref "IC33") (pin "AN3") (pinfunction "MGTHTXN0_224_AN3") (pintype "output"))
    )
    (net (code "119") (name "/TxFD_1_C_P") (class "Default")
      (node (ref "C249") (pin "1") (pinfunction "1_1") (pintype "passive"))
      (node (ref "IC33") (pin "AN4") (pinfunction "MGTHTXP0_224_AN4") (pintype "output"))
    )
    (net (code "120") (name "/TxFD_2_C_N") (class "Default")
      (node (ref "C248") (pin "1") (pinfunction "1_1") (pintype "passive"))
      (node (ref "IC33") (pin "AL3") (pinfunction "MGTHTXN2_224_AL3") (pintype "output"))
    )
    (net (code "121") (name "/TxFD_2_C_P") (class "Default")
      (node (ref "C247") (pin "1") (pinfunction "1_1") (pintype "passive"))
      (node (ref "IC33") (pin "AL4") (pinfunction "MGTHTXP2_224_AL4") (pintype "output"))
    )
    (net (code "122") (name "/TxFD_3_C_N") (class "Default")
      (node (ref "C260") (pin "1") (pinfunction "1_1") (pintype "passive"))
      (node (ref "IC33") (pin "AH5") (pinfunction "MGTHTXN0_225_AH5") (pintype "output"))
    )
    (net (code "123") (name "/TxFD_3_C_P") (class "Default")
      (node (ref "C261") (pin "1") (pinfunction "1_1") (pintype "passive"))
      (node (ref "IC33") (pin "AH6") (pinfunction "MGTHTXP0_225_AH6") (pintype "output"))
    )
    (net (code "124") (name "/TxFD_4_C_N") (class "Default")
      (node (ref "C246") (pin "1") (pinfunction "1_1") (pintype "passive"))
      (node (ref "IC33") (pin "AE3") (pinfunction "MGTHTXN2_225_AE3") (pintype "output"))
    )
    (net (code "125") (name "/TxFD_4_C_P") (class "Default")
      (node (ref "C245") (pin "1") (pinfunction "1_1") (pintype "passive"))
      (node (ref "IC33") (pin "AE4") (pinfunction "MGTHTXP2_225_AE4") (pintype "output"))
    )
    (net (code "126") (name "/TxFD_5_C_N") (class "Default")
      (node (ref "C252") (pin "2") (pinfunction "2_2") (pintype "passive"))
      (node (ref "IC33") (pin "AA3") (pinfunction "MGTHTXN0_226_AA3") (pintype "output"))
    )
    (net (code "127") (name "/TxFD_5_C_P") (class "Default")
      (node (ref "C251") (pin "2") (pinfunction "2_2") (pintype "passive"))
      (node (ref "IC33") (pin "AA4") (pinfunction "MGTHTXP0_226_AA4") (pintype "output"))
    )
    (net (code "128") (name "/TxFD_6_C_N") (class "Default")
      (node (ref "C256") (pin "2") (pinfunction "2_2") (pintype "passive"))
      (node (ref "IC33") (pin "U3") (pinfunction "MGTHTXN2_226_U3") (pintype "output"))
    )
    (net (code "129") (name "/TxFD_6_C_P") (class "Default")
      (node (ref "C255") (pin "2") (pinfunction "2_2") (pintype "passive"))
      (node (ref "IC33") (pin "U4") (pinfunction "MGTHTXP2_226_U4") (pintype "output"))
    )
    (net (code "130") (name "/TxFD_7_C_N") (class "Default")
      (node (ref "C240") (pin "1") (pinfunction "1_1") (pintype "passive"))
      (node (ref "IC33") (pin "AM5") (pinfunction "MGTHTXN1_224_AM5") (pintype "output"))
    )
    (net (code "131") (name "/TxFD_7_C_P") (class "Default")
      (node (ref "C239") (pin "1") (pinfunction "1_1") (pintype "passive"))
      (node (ref "IC33") (pin "AM6") (pinfunction "MGTHTXP1_224_AM6") (pintype "output"))
    )
    (net (code "132") (name "/TxFD_8_C_N") (class "Default")
      (node (ref "C244") (pin "1") (pinfunction "1_1") (pintype "passive"))
      (node (ref "IC33") (pin "AK5") (pinfunction "MGTHTXN3_224_AK5") (pintype "output"))
    )
    (net (code "133") (name "/TxFD_8_C_P") (class "Default")
      (node (ref "C243") (pin "1") (pinfunction "1_1") (pintype "passive"))
      (node (ref "IC33") (pin "AK6") (pinfunction "MGTHTXP3_224_AK6") (pintype "output"))
    )
    (net (code "134") (name "/TxFD_9_C_N") (class "Default")
      (node (ref "C242") (pin "1") (pinfunction "1_1") (pintype "passive"))
      (node (ref "IC33") (pin "AG3") (pinfunction "MGTHTXN1_225_AG3") (pintype "output"))
    )
    (net (code "135") (name "/TxFD_9_C_P") (class "Default")
      (node (ref "C241") (pin "1") (pinfunction "1_1") (pintype "passive"))
      (node (ref "IC33") (pin "AG4") (pinfunction "MGTHTXP1_225_AG4") (pintype "output"))
    )
    (net (code "136") (name "/TxFD_10_C_N") (class "Default")
      (node (ref "C238") (pin "1") (pinfunction "1_1") (pintype "passive"))
      (node (ref "IC33") (pin "AC3") (pinfunction "MGTHTXN3_225_AC3") (pintype "output"))
    )
    (net (code "137") (name "/TxFD_10_C_P") (class "Default")
      (node (ref "C237") (pin "1") (pinfunction "1_1") (pintype "passive"))
      (node (ref "IC33") (pin "AC4") (pinfunction "MGTHTXP3_225_AC4") (pintype "output"))
    )
    (net (code "138") (name "/TxFD_11_C_N") (class "Default")
      (node (ref "C254") (pin "2") (pinfunction "2_2") (pintype "passive"))
      (node (ref "IC33") (pin "W3") (pinfunction "MGTHTXN1_226_W3") (pintype "output"))
    )
    (net (code "139") (name "/TxFD_11_C_P") (class "Default")
      (node (ref "C253") (pin "2") (pinfunction "2_2") (pintype "passive"))
      (node (ref "IC33") (pin "W4") (pinfunction "MGTHTXP1_226_W4") (pintype "output"))
    )
    (net (code "140") (name "/TxFD_12_C_N") (class "Default")
      (node (ref "C258") (pin "2") (pinfunction "2_2") (pintype "passive"))
      (node (ref "IC33") (pin "R3") (pinfunction "MGTHTXN3_226_R3") (pintype "output"))
    )
    (net (code "141") (name "/TxFD_12_C_P") (class "Default")
      (node (ref "C257") (pin "2") (pinfunction "2_2") (pintype "passive"))
      (node (ref "IC33") (pin "R4") (pinfunction "MGTHTXP3_226_R4") (pintype "output"))
    )
    (net (code "148") (name "GND") (class "Default")
      (node (ref "C259") (pin "1") (pinfunction "1_1") (pintype "passive"))
      (node (ref "J18") (pin "2") (pinfunction "2_2") (pintype "bidirectional"))
      (node (ref "J19") (pin "2") (pinfunction "2_2") (pintype "bidirectional"))
      (node (ref "J20") (pin "2") (pinfunction "2_2") (pintype "bidirectional"))
      (node (ref "J21") (pin "2") (pinfunction "2_2") (pintype "bidirectional"))
      (node (ref "OSC2") (pin "3") (pinfunction "GND_3") (pintype "power_in"))
      (node (ref "R256") (pin "1") (pinfunction "1_1") (pintype "passive"))
      (node (ref "R257") (pin "1") (pinfunction "1_1") (pintype "passive"))
    )
    (net (code "149") (name "Net-(C213-Pad1)") (class "Default")
      (node (ref "C213") (pin "1") (pinfunction "1_1") (pintype "passive"))
      (node (ref "R112") (pin "2") (pinfunction "2_2") (pintype "passive"))
    )
    (net (code "150") (name "Net-(C214-Pad1)") (class "Default")
      (node (ref "C214") (pin "1") (pinfunction "1_1") (pintype "passive"))
      (node (ref "R113") (pin "2") (pinfunction "2_2") (pintype "passive"))
    )
    (net (code "151") (name "Net-(OSC2-CLK+)") (class "Default")
      (node (ref "OSC2") (pin "4") (pinfunction "CLK+_4") (pintype "output"))
      (node (ref "R112") (pin "1") (pinfunction "1_1") (pintype "passive"))
      (node (ref "R256") (pin "2") (pinfunction "2_2") (pintype "passive"))
    )
    (net (code "152") (name "Net-(OSC2-CLK-)") (class "Default")
      (node (ref "OSC2") (pin "5") (pinfunction "CLK-_5") (pintype "output"))
      (node (ref "R113") (pin "1") (pinfunction "1_1") (pintype "passive"))
      (node (ref "R257") (pin "2") (pinfunction "2_2") (pintype "passive"))
    )
    (net (code "153") (name "P3V3") (class "Default")
      (node (ref "L19") (pin "1") (pinfunction "1_1") (pintype "passive"))
    )
    (net (code "154") (name "unconnected-(IC33K-MGTREFCLK0N_224-PadAF5)") (class "Default")
      (node (ref "IC33") (pin "AF5") (pinfunction "MGTREFCLK0N_224_AF5") (pintype "input+no_connect"))
    )
    (net (code "155") (name "unconnected-(IC33K-MGTREFCLK0P_224-PadAF6)") (class "Default")
      (node (ref "IC33") (pin "AF6") (pinfunction "MGTREFCLK0P_224_AF6") (pintype "input+no_connect"))
    )
    (net (code "156") (name "unconnected-(OSC2-NC-Pad1)") (class "Default")
      (node (ref "OSC2") (pin "1") (pinfunction "NC_1") (pintype "passive+no_connect"))
    )
  )
)
